# scheme.net
KiCad netlist of a schematic drawn in EAGLE
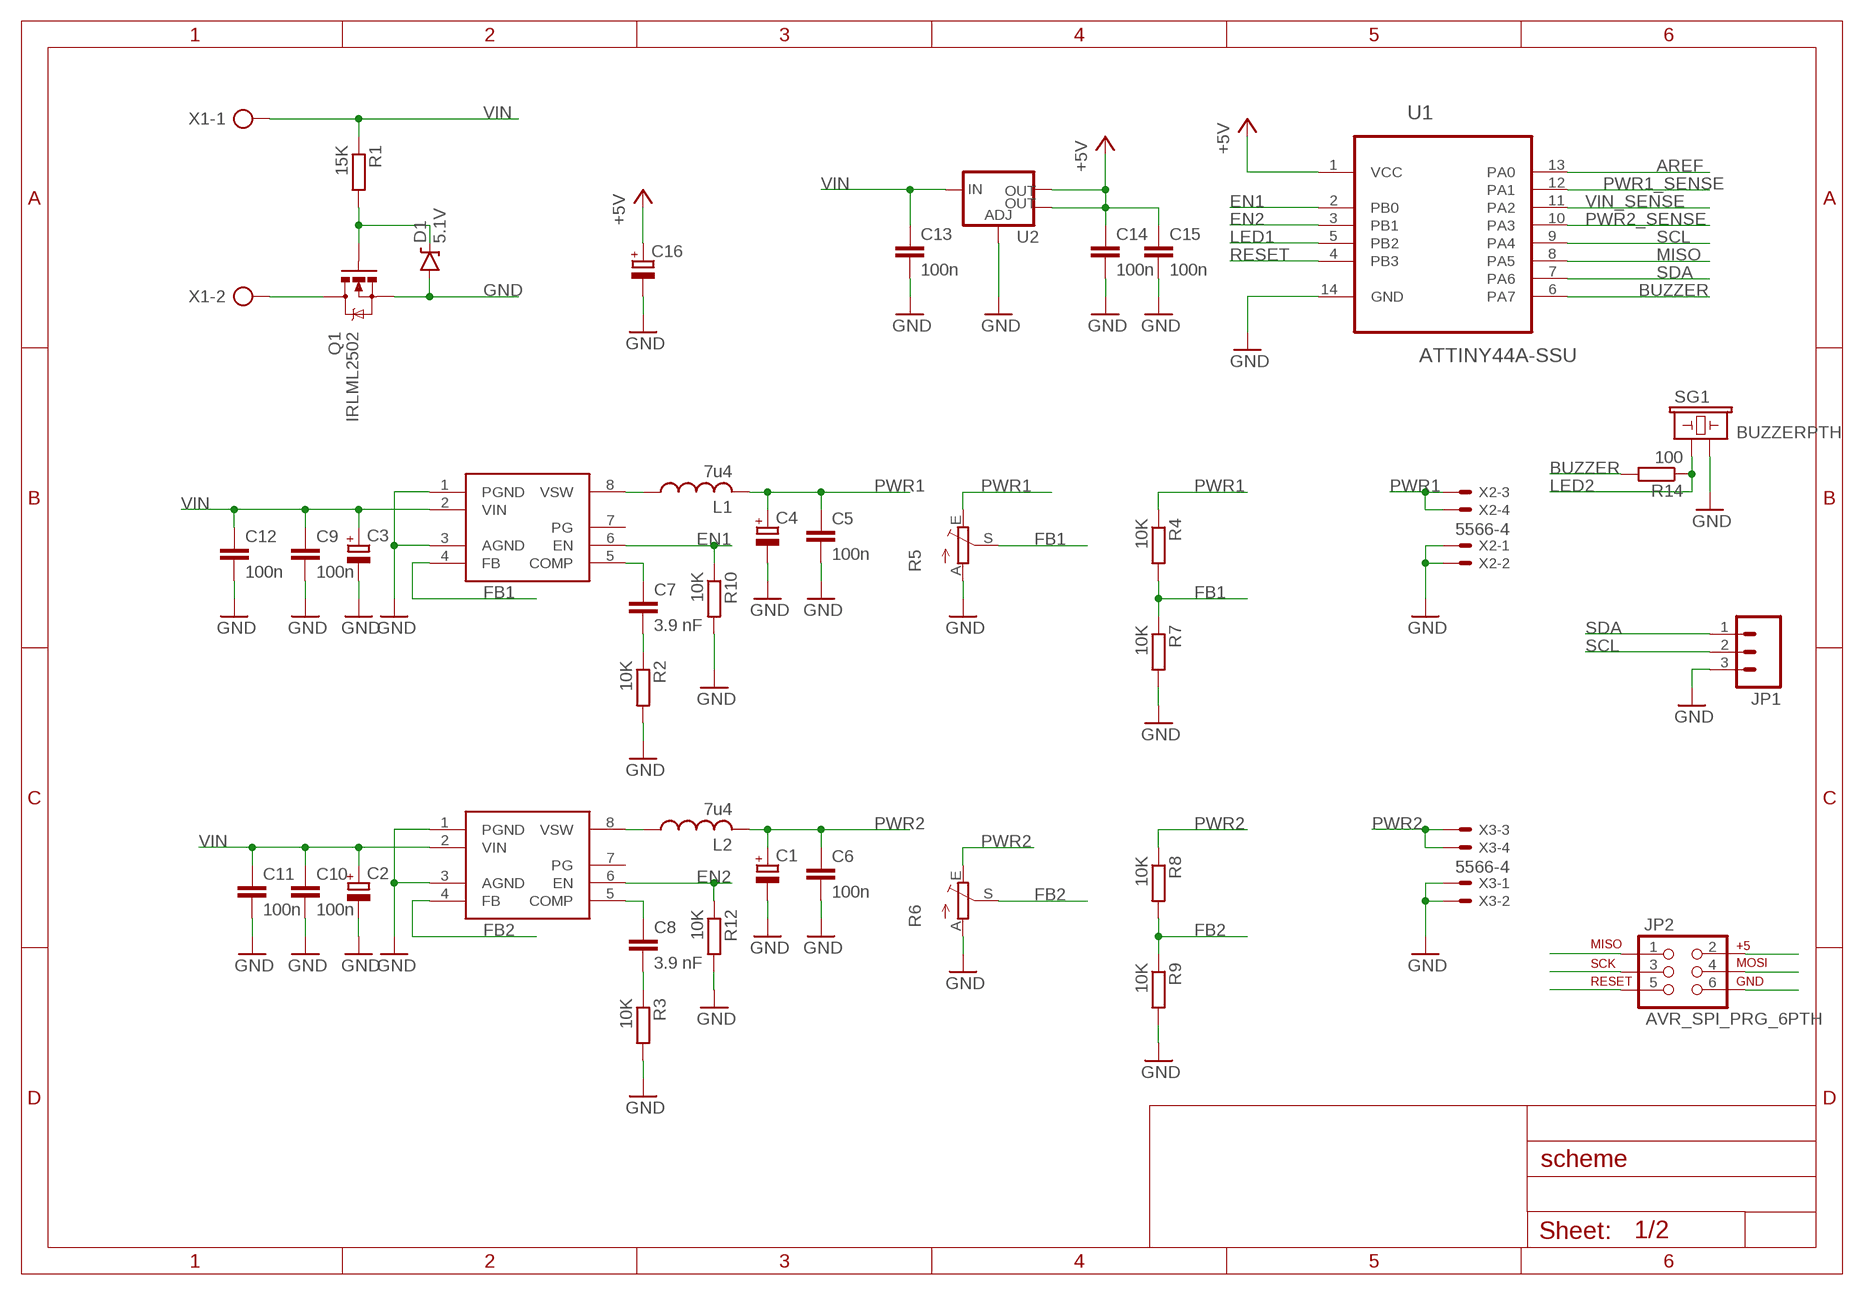
[diagram p0: schematic, sheet 1]
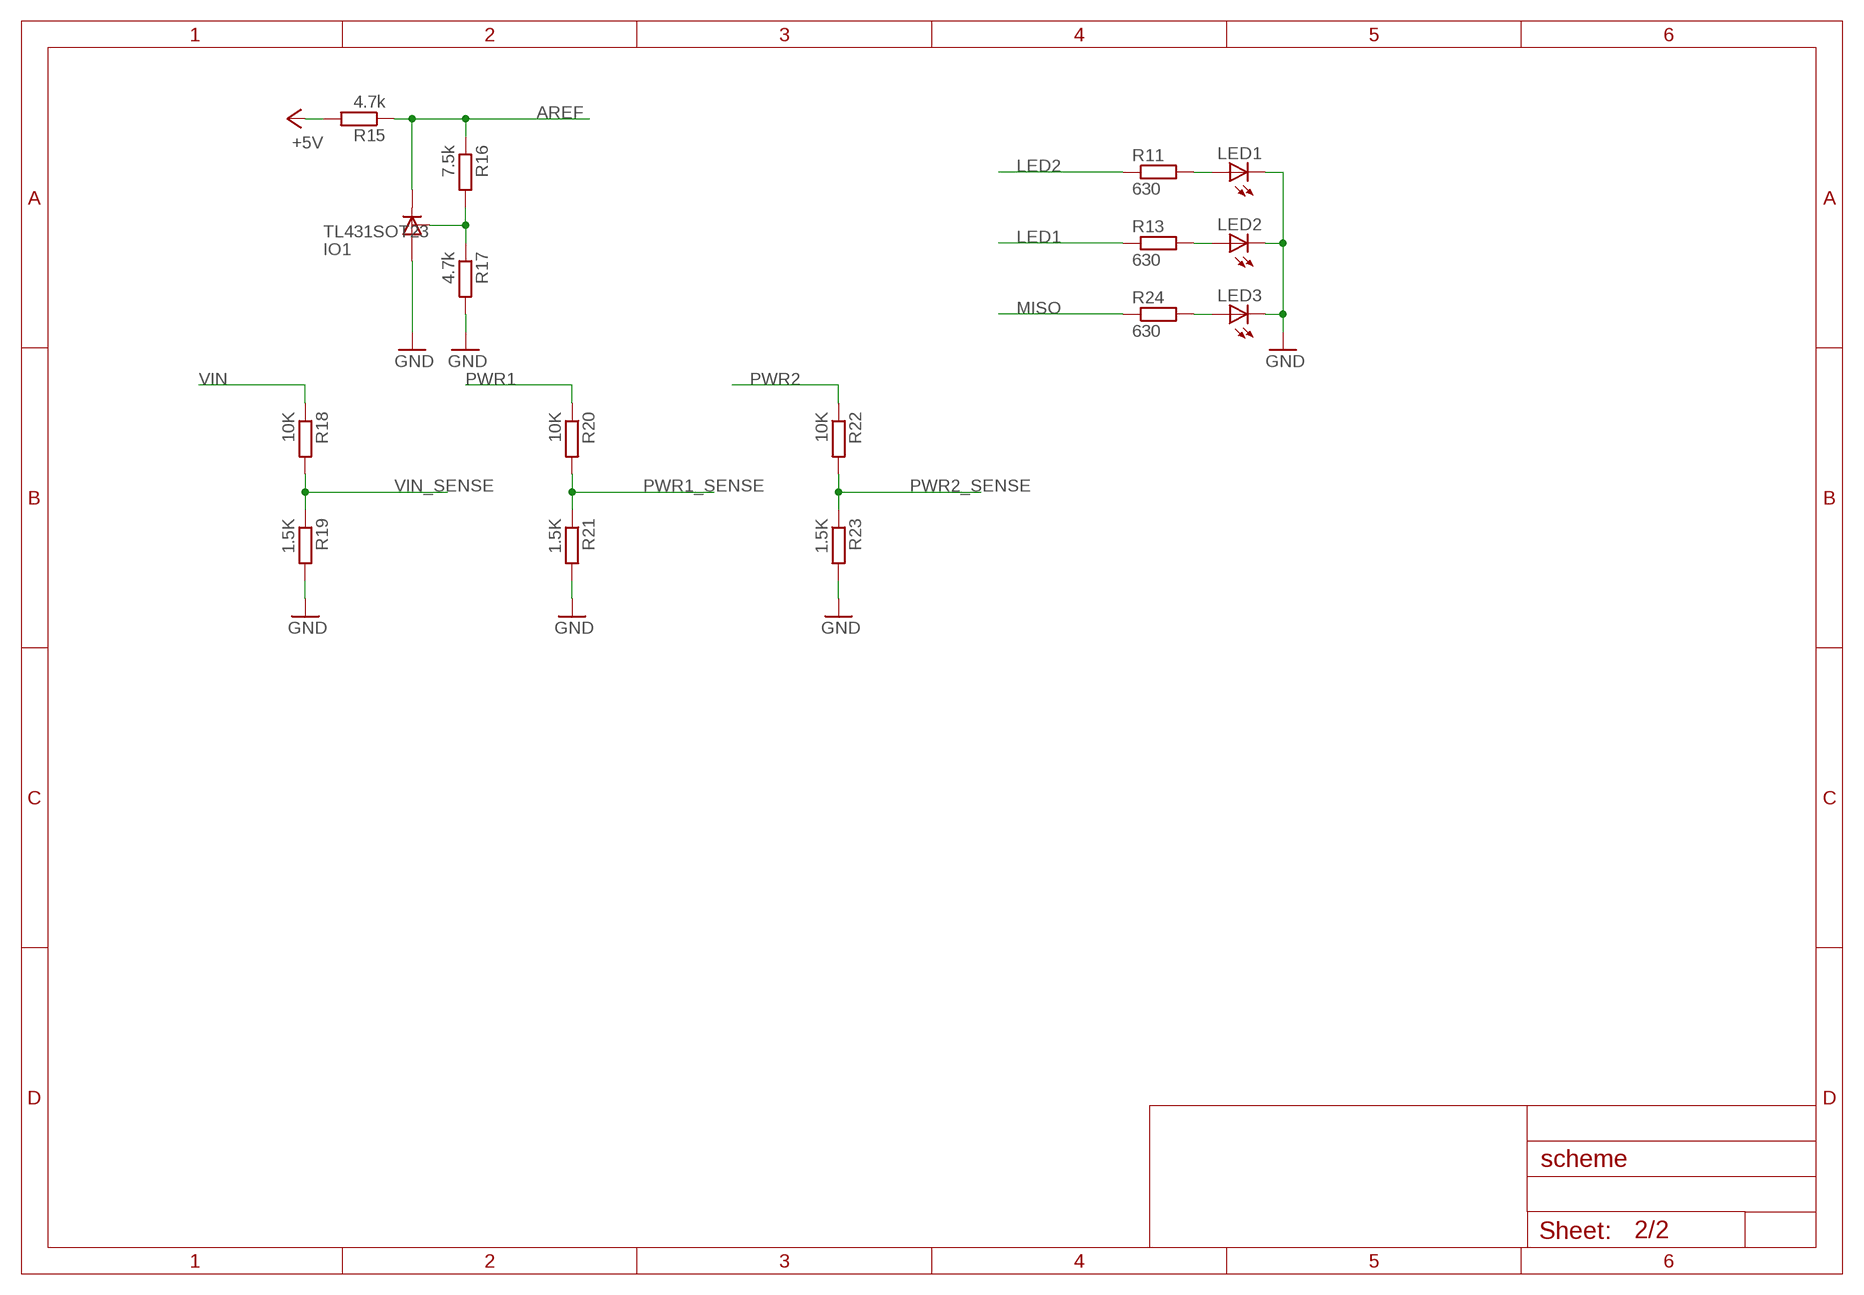
[diagram p1: schematic, sheet 2]

(export (version "E")
  (design (tool "Eeschema 10.0.6"))
  (components
    (comp (ref "C1")
      (value "CPOL-EUD/7343-31R")
      (footprint "eagle-import:D_7343-31R")
      (libsource (lib "eagle-import") (part "CPOL-EUD/7343-31R"))
    )
    (comp (ref "C2")
      (value "CPOL-EUD/7343-31R")
      (footprint "eagle-import:D_7343-31R")
      (libsource (lib "eagle-import") (part "CPOL-EUD/7343-31R"))
    )
    (comp (ref "C3")
      (value "CPOL-EUD/7343-31R")
      (footprint "eagle-import:D_7343-31R")
      (libsource (lib "eagle-import") (part "CPOL-EUD/7343-31R"))
    )
    (comp (ref "C4")
      (value "CPOL-EUD/7343-31R")
      (footprint "eagle-import:D_7343-31R")
      (libsource (lib "eagle-import") (part "CPOL-EUD/7343-31R"))
    )
    (comp (ref "C5")
      (value "100n")
      (footprint "eagle-import:C0805")
      (libsource (lib "eagle-import") (part "C-EUC0805"))
    )
    (comp (ref "C6")
      (value "100n")
      (footprint "eagle-import:C0805")
      (libsource (lib "eagle-import") (part "C-EUC0805"))
    )
    (comp (ref "C7")
      (value "3.9 nF")
      (footprint "eagle-import:C0805")
      (libsource (lib "eagle-import") (part "C-EUC0805"))
    )
    (comp (ref "C8")
      (value "3.9 nF")
      (footprint "eagle-import:C0805")
      (libsource (lib "eagle-import") (part "C-EUC0805"))
    )
    (comp (ref "C9")
      (value "100n")
      (footprint "eagle-import:C0805")
      (libsource (lib "eagle-import") (part "C-EUC0805"))
    )
    (comp (ref "C10")
      (value "100n")
      (footprint "eagle-import:C0805")
      (libsource (lib "eagle-import") (part "C-EUC0805"))
    )
    (comp (ref "C11")
      (value "100n")
      (footprint "eagle-import:C0805")
      (libsource (lib "eagle-import") (part "C-EUC0805"))
    )
    (comp (ref "C12")
      (value "100n")
      (footprint "eagle-import:C0805")
      (libsource (lib "eagle-import") (part "C-EUC0805"))
    )
    (comp (ref "C13")
      (value "100n")
      (footprint "eagle-import:C0805")
      (libsource (lib "eagle-import") (part "C-EUC0805"))
    )
    (comp (ref "C14")
      (value "100n")
      (footprint "eagle-import:C0805")
      (libsource (lib "eagle-import") (part "C-EUC0805"))
    )
    (comp (ref "C15")
      (value "100n")
      (footprint "eagle-import:C0805")
      (libsource (lib "eagle-import") (part "C-EUC0805"))
    )
    (comp (ref "C16")
      (value "CPOL-EUD/7343-31R")
      (footprint "eagle-import:D_7343-31R")
      (libsource (lib "eagle-import") (part "CPOL-EUD/7343-31R"))
    )
    (comp (ref "D1")
      (value "5.1V")
      (footprint "eagle-import:SOD-323")
      (libsource (lib "eagle-import") (part "DIODE-ZENER5.6V"))
    )
    (comp (ref "JP1")
      (value "M03PTH")
      (footprint "eagle-import:1X03")
      (libsource (lib "eagle-import") (part "M03PTH"))
    )
    (comp (ref "JP2")
      (value "AVR_SPI_PRG_6PTH")
      (footprint "eagle-import:2X3")
      (libsource (lib "eagle-import") (part "AVR_SPI_PRG_6PTH"))
    )
    (comp (ref "L1")
      (value "7u4")
      (footprint "eagle-import:CDRH6D38")
      (libsource (lib "eagle-import") (part "L-USCDRH6D38"))
    )
    (comp (ref "L2")
      (value "7u4")
      (footprint "eagle-import:CDRH6D38")
      (libsource (lib "eagle-import") (part "L-USCDRH6D38"))
    )
    (comp (ref "Q1")
      (value "IRLML2502")
      (footprint "eagle-import:SOT23-3")
      (libsource (lib "eagle-import") (part "MOSFET-NCHANNELAO3404A"))
    )
    (comp (ref "R1")
      (value "15K")
      (footprint "eagle-import:R0805")
      (libsource (lib "eagle-import") (part "R-EU_R0805"))
    )
    (comp (ref "R2")
      (value "10K")
      (footprint "eagle-import:R0805")
      (libsource (lib "eagle-import") (part "R-EU_R0805"))
    )
    (comp (ref "R3")
      (value "10K")
      (footprint "eagle-import:R0805")
      (libsource (lib "eagle-import") (part "R-EU_R0805"))
    )
    (comp (ref "R4")
      (value "10K")
      (footprint "eagle-import:R0805")
      (libsource (lib "eagle-import") (part "R-EU_R0805"))
    )
    (comp (ref "R5")
      (value "TRIM_EU-RJ9W")
      (footprint "eagle-import:RJ9W")
      (libsource (lib "eagle-import") (part "TRIM_EU-RJ9W"))
    )
    (comp (ref "R6")
      (value "TRIM_EU-RJ9W")
      (footprint "eagle-import:RJ9W")
      (libsource (lib "eagle-import") (part "TRIM_EU-RJ9W"))
    )
    (comp (ref "R7")
      (value "10K")
      (footprint "eagle-import:R0805")
      (libsource (lib "eagle-import") (part "R-EU_R0805"))
    )
    (comp (ref "R8")
      (value "10K")
      (footprint "eagle-import:R0805")
      (libsource (lib "eagle-import") (part "R-EU_R0805"))
    )
    (comp (ref "R9")
      (value "10K")
      (footprint "eagle-import:R0805")
      (libsource (lib "eagle-import") (part "R-EU_R0805"))
    )
    (comp (ref "R10")
      (value "10K")
      (footprint "eagle-import:R0805")
      (libsource (lib "eagle-import") (part "R-EU_R0805"))
    )
    (comp (ref "R12")
      (value "10K")
      (footprint "eagle-import:R0805")
      (libsource (lib "eagle-import") (part "R-EU_R0805"))
    )
    (comp (ref "R14")
      (value "100")
      (footprint "eagle-import:R0805")
      (libsource (lib "eagle-import") (part "R-EU_R0805"))
    )
    (comp (ref "SG1")
      (value "BUZZERPTH")
      (footprint "eagle-import:BUZZER-12MM")
      (libsource (lib "eagle-import") (part "BUZZERPTH"))
    )
    (comp (ref "U$1")
      (value "NCP3170")
      (footprint "eagle-import:SO08")
      (libsource (lib "eagle-import") (part "NCP3170"))
    )
    (comp (ref "U$2")
      (value "NCP3170")
      (footprint "eagle-import:SO08")
      (libsource (lib "eagle-import") (part "NCP3170"))
    )
    (comp (ref "U1")
      (value "ATTINY44A-SSU")
      (footprint "eagle-import:SOIC127P600X175-14N")
      (libsource (lib "eagle-import") (part "ATTINY44A-SSU"))
    )
    (comp (ref "U2")
      (value "V_REG_LM1117SOT223")
      (footprint "eagle-import:SOT223")
      (libsource (lib "eagle-import") (part "V_REG_LM1117SOT223"))
    )
    (comp (ref "X1")
      (value "AK500/2")
      (footprint "eagle-import:AK500_2")
      (libsource (lib "eagle-import") (part "AK500/2"))
    )
    (comp (ref "X2")
      (value "5566-4")
      (footprint "eagle-import:5566-4")
      (libsource (lib "eagle-import") (part "5566-4"))
    )
    (comp (ref "X3")
      (value "5566-4")
      (footprint "eagle-import:5566-4")
      (libsource (lib "eagle-import") (part "5566-4"))
    )
    (comp (ref "IO1")
      (value "TL431SOT23")
      (footprint "eagle-import:SOT23")
      (fields (field (name "MPN") "TL431BFDT"))
      (libsource (lib "eagle-import") (part "TL431SOT23"))
    )
    (comp (ref "LED1")
      (value "LEDCHIPLED_0805")
      (footprint "eagle-import:CHIPLED_0805")
      (libsource (lib "eagle-import") (part "LEDCHIPLED_0805"))
    )
    (comp (ref "LED2")
      (value "LEDCHIPLED_0805")
      (footprint "eagle-import:CHIPLED_0805")
      (libsource (lib "eagle-import") (part "LEDCHIPLED_0805"))
    )
    (comp (ref "LED3")
      (value "LEDCHIPLED_0805")
      (footprint "eagle-import:CHIPLED_0805")
      (libsource (lib "eagle-import") (part "LEDCHIPLED_0805"))
    )
    (comp (ref "R11")
      (value "630")
      (footprint "eagle-import:R0805")
      (libsource (lib "eagle-import") (part "R-EU_R0805"))
    )
    (comp (ref "R13")
      (value "630")
      (footprint "eagle-import:R0805")
      (libsource (lib "eagle-import") (part "R-EU_R0805"))
    )
    (comp (ref "R15")
      (value "4.7k")
      (footprint "eagle-import:R0805")
      (libsource (lib "eagle-import") (part "R-EU_R0805"))
    )
    (comp (ref "R16")
      (value "7.5k")
      (footprint "eagle-import:R0805")
      (libsource (lib "eagle-import") (part "R-EU_R0805"))
    )
    (comp (ref "R17")
      (value "4.7k")
      (footprint "eagle-import:R0805")
      (libsource (lib "eagle-import") (part "R-EU_R0805"))
    )
    (comp (ref "R18")
      (value "10K")
      (footprint "eagle-import:R0805")
      (libsource (lib "eagle-import") (part "R-EU_R0805"))
    )
    (comp (ref "R19")
      (value "1.5K")
      (footprint "eagle-import:R0805")
      (libsource (lib "eagle-import") (part "R-EU_R0805"))
    )
    (comp (ref "R20")
      (value "10K")
      (footprint "eagle-import:R0805")
      (libsource (lib "eagle-import") (part "R-EU_R0805"))
    )
    (comp (ref "R21")
      (value "1.5K")
      (footprint "eagle-import:R0805")
      (libsource (lib "eagle-import") (part "R-EU_R0805"))
    )
    (comp (ref "R22")
      (value "10K")
      (footprint "eagle-import:R0805")
      (libsource (lib "eagle-import") (part "R-EU_R0805"))
    )
    (comp (ref "R23")
      (value "1.5K")
      (footprint "eagle-import:R0805")
      (libsource (lib "eagle-import") (part "R-EU_R0805"))
    )
    (comp (ref "R24")
      (value "630")
      (footprint "eagle-import:R0805")
      (libsource (lib "eagle-import") (part "R-EU_R0805"))
    )
  )
  (nets
    (net (code "1") (name "+5V") (class "Default")
      (node (ref "C14") (pin "1") (pinfunction "1_1") (pintype "passive"))
      (node (ref "C15") (pin "1") (pinfunction "1_1") (pintype "passive"))
      (node (ref "C16") (pin "+") (pinfunction "+_+") (pintype "passive"))
      (node (ref "JP2") (pin "2") (pinfunction "2_2") (pintype "passive"))
      (node (ref "R15") (pin "2") (pinfunction "2_2") (pintype "passive"))
      (node (ref "U1") (pin "1") (pinfunction "VCC_1") (pintype "power_in"))
      (node (ref "U2") (pin "2") (pinfunction "OUT_2") (pintype "output"))
      (node (ref "U2") (pin "4") (pinfunction "OUT_4") (pintype "output"))
    )
    (net (code "2") (name "AREF") (class "Default")
      (node (ref "IO1") (pin "1") (pinfunction "C_1") (pintype "bidirectional"))
      (node (ref "R15") (pin "1") (pinfunction "1_1") (pintype "passive"))
      (node (ref "R16") (pin "1") (pinfunction "1_1") (pintype "passive"))
      (node (ref "U1") (pin "13") (pinfunction "PA0_13") (pintype "bidirectional"))
    )
    (net (code "3") (name "BUZZER") (class "Default")
      (node (ref "R14") (pin "2") (pinfunction "2_2") (pintype "passive"))
      (node (ref "U1") (pin "6") (pinfunction "PA7_6") (pintype "bidirectional"))
    )
    (net (code "4") (name "EN1") (class "Default")
      (node (ref "R10") (pin "1") (pinfunction "1_1") (pintype "passive"))
      (node (ref "U$2") (pin "6") (pinfunction "EN_6") (pintype "input"))
      (node (ref "U1") (pin "2") (pinfunction "PB0_2") (pintype "bidirectional"))
    )
    (net (code "5") (name "EN2") (class "Default")
      (node (ref "R12") (pin "1") (pinfunction "1_1") (pintype "passive"))
      (node (ref "U$1") (pin "6") (pinfunction "EN_6") (pintype "input"))
      (node (ref "U1") (pin "3") (pinfunction "PB1_3") (pintype "bidirectional"))
    )
    (net (code "6") (name "FB1") (class "Default")
      (node (ref "R4") (pin "2") (pinfunction "2_2") (pintype "passive"))
      (node (ref "R5") (pin "S") (pinfunction "S_S") (pintype "passive"))
      (node (ref "R7") (pin "1") (pinfunction "1_1") (pintype "passive"))
      (node (ref "U$2") (pin "4") (pinfunction "FB_4") (pintype "input"))
    )
    (net (code "7") (name "FB2") (class "Default")
      (node (ref "R6") (pin "S") (pinfunction "S_S") (pintype "passive"))
      (node (ref "R8") (pin "2") (pinfunction "2_2") (pintype "passive"))
      (node (ref "R9") (pin "1") (pinfunction "1_1") (pintype "passive"))
      (node (ref "U$1") (pin "4") (pinfunction "FB_4") (pintype "input"))
    )
    (net (code "8") (name "GND") (class "Default")
      (node (ref "C1") (pin "-") (pinfunction "-_-") (pintype "passive"))
      (node (ref "C10") (pin "2") (pinfunction "2_2") (pintype "passive"))
      (node (ref "C11") (pin "2") (pinfunction "2_2") (pintype "passive"))
      (node (ref "C12") (pin "2") (pinfunction "2_2") (pintype "passive"))
      (node (ref "C13") (pin "2") (pinfunction "2_2") (pintype "passive"))
      (node (ref "C14") (pin "2") (pinfunction "2_2") (pintype "passive"))
      (node (ref "C15") (pin "2") (pinfunction "2_2") (pintype "passive"))
      (node (ref "C16") (pin "-") (pinfunction "-_-") (pintype "passive"))
      (node (ref "C2") (pin "-") (pinfunction "-_-") (pintype "passive"))
      (node (ref "C3") (pin "-") (pinfunction "-_-") (pintype "passive"))
      (node (ref "C4") (pin "-") (pinfunction "-_-") (pintype "passive"))
      (node (ref "C5") (pin "2") (pinfunction "2_2") (pintype "passive"))
      (node (ref "C6") (pin "2") (pinfunction "2_2") (pintype "passive"))
      (node (ref "C9") (pin "2") (pinfunction "2_2") (pintype "passive"))
      (node (ref "D1") (pin "A") (pinfunction "A_A") (pintype "passive"))
      (node (ref "IO1") (pin "3") (pinfunction "A_3") (pintype "bidirectional"))
      (node (ref "JP1") (pin "3") (pinfunction "3_3") (pintype "passive"))
      (node (ref "JP2") (pin "6") (pinfunction "6_6") (pintype "passive"))
      (node (ref "LED1") (pin "C") (pinfunction "C_C") (pintype "passive"))
      (node (ref "LED2") (pin "C") (pinfunction "C_C") (pintype "passive"))
      (node (ref "LED3") (pin "C") (pinfunction "C_C") (pintype "passive"))
      (node (ref "Q1") (pin "2") (pinfunction "S_2") (pintype "passive"))
      (node (ref "R10") (pin "2") (pinfunction "2_2") (pintype "passive"))
      (node (ref "R12") (pin "2") (pinfunction "2_2") (pintype "passive"))
      (node (ref "R17") (pin "2") (pinfunction "2_2") (pintype "passive"))
      (node (ref "R19") (pin "2") (pinfunction "2_2") (pintype "passive"))
      (node (ref "R2") (pin "2") (pinfunction "2_2") (pintype "passive"))
      (node (ref "R21") (pin "2") (pinfunction "2_2") (pintype "passive"))
      (node (ref "R23") (pin "2") (pinfunction "2_2") (pintype "passive"))
      (node (ref "R3") (pin "2") (pinfunction "2_2") (pintype "passive"))
      (node (ref "R5") (pin "A") (pinfunction "A_A") (pintype "passive"))
      (node (ref "R6") (pin "A") (pinfunction "A_A") (pintype "passive"))
      (node (ref "R7") (pin "2") (pinfunction "2_2") (pintype "passive"))
      (node (ref "R9") (pin "2") (pinfunction "2_2") (pintype "passive"))
      (node (ref "SG1") (pin "-") (pinfunction "2_-") (pintype "passive"))
      (node (ref "U$1") (pin "1") (pinfunction "PGND_1") (pintype "power_in"))
      (node (ref "U$1") (pin "3") (pinfunction "AGND_3") (pintype "power_in"))
      (node (ref "U$2") (pin "1") (pinfunction "PGND_1") (pintype "power_in"))
      (node (ref "U$2") (pin "3") (pinfunction "AGND_3") (pintype "power_in"))
      (node (ref "U1") (pin "14") (pinfunction "GND_14") (pintype "power_in"))
      (node (ref "U2") (pin "1") (pinfunction "ADJ_1") (pintype "input"))
      (node (ref "X2") (pin "1") (pinfunction "S_1") (pintype "passive"))
      (node (ref "X2") (pin "2") (pinfunction "S_2") (pintype "passive"))
      (node (ref "X3") (pin "1") (pinfunction "S_1") (pintype "passive"))
      (node (ref "X3") (pin "2") (pinfunction "S_2") (pintype "passive"))
    )
    (net (code "9") (name "LED1") (class "Default")
      (node (ref "R13") (pin "1") (pinfunction "1_1") (pintype "passive"))
      (node (ref "U1") (pin "5") (pinfunction "PB2_5") (pintype "bidirectional"))
    )
    (net (code "10") (name "LED2") (class "Default")
      (node (ref "R11") (pin "1") (pinfunction "1_1") (pintype "passive"))
      (node (ref "R14") (pin "1") (pinfunction "1_1") (pintype "passive"))
      (node (ref "SG1") (pin "+") (pinfunction "1_+") (pintype "passive"))
    )
    (net (code "11") (name "MISO") (class "Default")
      (node (ref "JP2") (pin "1") (pinfunction "1_1") (pintype "passive"))
      (node (ref "R24") (pin "1") (pinfunction "1_1") (pintype "passive"))
      (node (ref "U1") (pin "8") (pinfunction "PA5_8") (pintype "bidirectional"))
    )
    (net (code "12") (name "Net-(C7-Pad2)") (class "Default")
      (node (ref "C7") (pin "2") (pinfunction "2_2") (pintype "passive"))
      (node (ref "R2") (pin "1") (pinfunction "1_1") (pintype "passive"))
    )
    (net (code "13") (name "Net-(C8-Pad2)") (class "Default")
      (node (ref "C8") (pin "2") (pinfunction "2_2") (pintype "passive"))
      (node (ref "R3") (pin "1") (pinfunction "1_1") (pintype "passive"))
    )
    (net (code "14") (name "Net-(IO1-R)") (class "Default")
      (node (ref "IO1") (pin "2") (pinfunction "R_2") (pintype "bidirectional"))
      (node (ref "R16") (pin "2") (pinfunction "2_2") (pintype "passive"))
      (node (ref "R17") (pin "1") (pinfunction "1_1") (pintype "passive"))
    )
    (net (code "15") (name "Net-(LED1-PadA)") (class "Default")
      (node (ref "LED1") (pin "A") (pinfunction "A_A") (pintype "passive"))
      (node (ref "R11") (pin "2") (pinfunction "2_2") (pintype "passive"))
    )
    (net (code "16") (name "Net-(LED2-PadA)") (class "Default")
      (node (ref "LED2") (pin "A") (pinfunction "A_A") (pintype "passive"))
      (node (ref "R13") (pin "2") (pinfunction "2_2") (pintype "passive"))
    )
    (net (code "17") (name "Net-(LED3-PadA)") (class "Default")
      (node (ref "LED3") (pin "A") (pinfunction "A_A") (pintype "passive"))
      (node (ref "R24") (pin "2") (pinfunction "2_2") (pintype "passive"))
    )
    (net (code "18") (name "Net-(Q1-D)") (class "Default")
      (node (ref "Q1") (pin "3") (pinfunction "D_3") (pintype "passive"))
      (node (ref "X1") (pin "2") (pinfunction "KL_2") (pintype "passive"))
    )
    (net (code "19") (name "Net-(Q1-G)") (class "Default")
      (node (ref "D1") (pin "C") (pinfunction "C_C") (pintype "passive"))
      (node (ref "Q1") (pin "1") (pinfunction "G_1") (pintype "passive"))
      (node (ref "R1") (pin "2") (pinfunction "2_2") (pintype "passive"))
    )
    (net (code "20") (name "Net-(U$1-COMP)") (class "Default")
      (node (ref "C8") (pin "1") (pinfunction "1_1") (pintype "passive"))
      (node (ref "U$1") (pin "5") (pinfunction "COMP_5") (pintype "bidirectional"))
    )
    (net (code "21") (name "Net-(U$1-VSW)") (class "Default")
      (node (ref "L2") (pin "1") (pinfunction "1_1") (pintype "passive"))
      (node (ref "U$1") (pin "8") (pinfunction "VSW_8") (pintype "power_in"))
    )
    (net (code "22") (name "Net-(U$2-COMP)") (class "Default")
      (node (ref "C7") (pin "1") (pinfunction "1_1") (pintype "passive"))
      (node (ref "U$2") (pin "5") (pinfunction "COMP_5") (pintype "bidirectional"))
    )
    (net (code "23") (name "Net-(U$2-VSW)") (class "Default")
      (node (ref "L1") (pin "1") (pinfunction "1_1") (pintype "passive"))
      (node (ref "U$2") (pin "8") (pinfunction "VSW_8") (pintype "power_in"))
    )
    (net (code "24") (name "PWR1") (class "Default")
      (node (ref "C4") (pin "+") (pinfunction "+_+") (pintype "passive"))
      (node (ref "C5") (pin "1") (pinfunction "1_1") (pintype "passive"))
      (node (ref "L1") (pin "2") (pinfunction "2_2") (pintype "passive"))
      (node (ref "R20") (pin "1") (pinfunction "1_1") (pintype "passive"))
      (node (ref "R4") (pin "1") (pinfunction "1_1") (pintype "passive"))
      (node (ref "R5") (pin "E") (pinfunction "E_E") (pintype "passive"))
      (node (ref "X2") (pin "3") (pinfunction "S_3") (pintype "passive"))
      (node (ref "X2") (pin "4") (pinfunction "S_4") (pintype "passive"))
    )
    (net (code "25") (name "PWR1_SENSE") (class "Default")
      (node (ref "R20") (pin "2") (pinfunction "2_2") (pintype "passive"))
      (node (ref "R21") (pin "1") (pinfunction "1_1") (pintype "passive"))
      (node (ref "U1") (pin "12") (pinfunction "PA1_12") (pintype "bidirectional"))
    )
    (net (code "26") (name "PWR2") (class "Default")
      (node (ref "C1") (pin "+") (pinfunction "+_+") (pintype "passive"))
      (node (ref "C6") (pin "1") (pinfunction "1_1") (pintype "passive"))
      (node (ref "L2") (pin "2") (pinfunction "2_2") (pintype "passive"))
      (node (ref "R22") (pin "1") (pinfunction "1_1") (pintype "passive"))
      (node (ref "R6") (pin "E") (pinfunction "E_E") (pintype "passive"))
      (node (ref "R8") (pin "1") (pinfunction "1_1") (pintype "passive"))
      (node (ref "X3") (pin "3") (pinfunction "S_3") (pintype "passive"))
      (node (ref "X3") (pin "4") (pinfunction "S_4") (pintype "passive"))
    )
    (net (code "27") (name "PWR2_SENSE") (class "Default")
      (node (ref "R22") (pin "2") (pinfunction "2_2") (pintype "passive"))
      (node (ref "R23") (pin "1") (pinfunction "1_1") (pintype "passive"))
      (node (ref "U1") (pin "10") (pinfunction "PA3_10") (pintype "bidirectional"))
    )
    (net (code "28") (name "RESET") (class "Default")
      (node (ref "JP2") (pin "5") (pinfunction "5_5") (pintype "passive"))
      (node (ref "U1") (pin "4") (pinfunction "PB3_4") (pintype "bidirectional"))
    )
    (net (code "29") (name "SCL") (class "Default")
      (node (ref "JP1") (pin "2") (pinfunction "2_2") (pintype "passive"))
      (node (ref "JP2") (pin "3") (pinfunction "3_3") (pintype "passive"))
      (node (ref "U1") (pin "9") (pinfunction "PA4_9") (pintype "bidirectional"))
    )
    (net (code "30") (name "SDA") (class "Default")
      (node (ref "JP1") (pin "1") (pinfunction "1_1") (pintype "passive"))
      (node (ref "JP2") (pin "4") (pinfunction "4_4") (pintype "passive"))
      (node (ref "U1") (pin "7") (pinfunction "PA6_7") (pintype "bidirectional"))
    )
    (net (code "31") (name "VIN") (class "Default")
      (node (ref "C10") (pin "1") (pinfunction "1_1") (pintype "passive"))
      (node (ref "C11") (pin "1") (pinfunction "1_1") (pintype "passive"))
      (node (ref "C12") (pin "1") (pinfunction "1_1") (pintype "passive"))
      (node (ref "C13") (pin "1") (pinfunction "1_1") (pintype "passive"))
      (node (ref "C2") (pin "+") (pinfunction "+_+") (pintype "passive"))
      (node (ref "C3") (pin "+") (pinfunction "+_+") (pintype "passive"))
      (node (ref "C9") (pin "1") (pinfunction "1_1") (pintype "passive"))
      (node (ref "R1") (pin "1") (pinfunction "1_1") (pintype "passive"))
      (node (ref "R18") (pin "1") (pinfunction "1_1") (pintype "passive"))
      (node (ref "U$1") (pin "2") (pinfunction "VIN_2") (pintype "power_in"))
      (node (ref "U$2") (pin "2") (pinfunction "VIN_2") (pintype "power_in"))
      (node (ref "U2") (pin "3") (pinfunction "IN_3") (pintype "input"))
      (node (ref "X1") (pin "1") (pinfunction "KL_1") (pintype "passive"))
    )
    (net (code "32") (name "VIN_SENSE") (class "Default")
      (node (ref "R18") (pin "2") (pinfunction "2_2") (pintype "passive"))
      (node (ref "R19") (pin "1") (pinfunction "1_1") (pintype "passive"))
      (node (ref "U1") (pin "11") (pinfunction "PA2_11") (pintype "bidirectional"))
    )
    (net (code "33") (name "unconnected-(U$1-PG-Pad7)") (class "Default")
      (node (ref "U$1") (pin "7") (pinfunction "PG_7") (pintype "output"))
    )
    (net (code "34") (name "unconnected-(U$2-PG-Pad7)") (class "Default")
      (node (ref "U$2") (pin "7") (pinfunction "PG_7") (pintype "output"))
    )
  )
)
